# Adder_Subtracter.net
KiCad netlist of a schematic drawn in Altium Designer
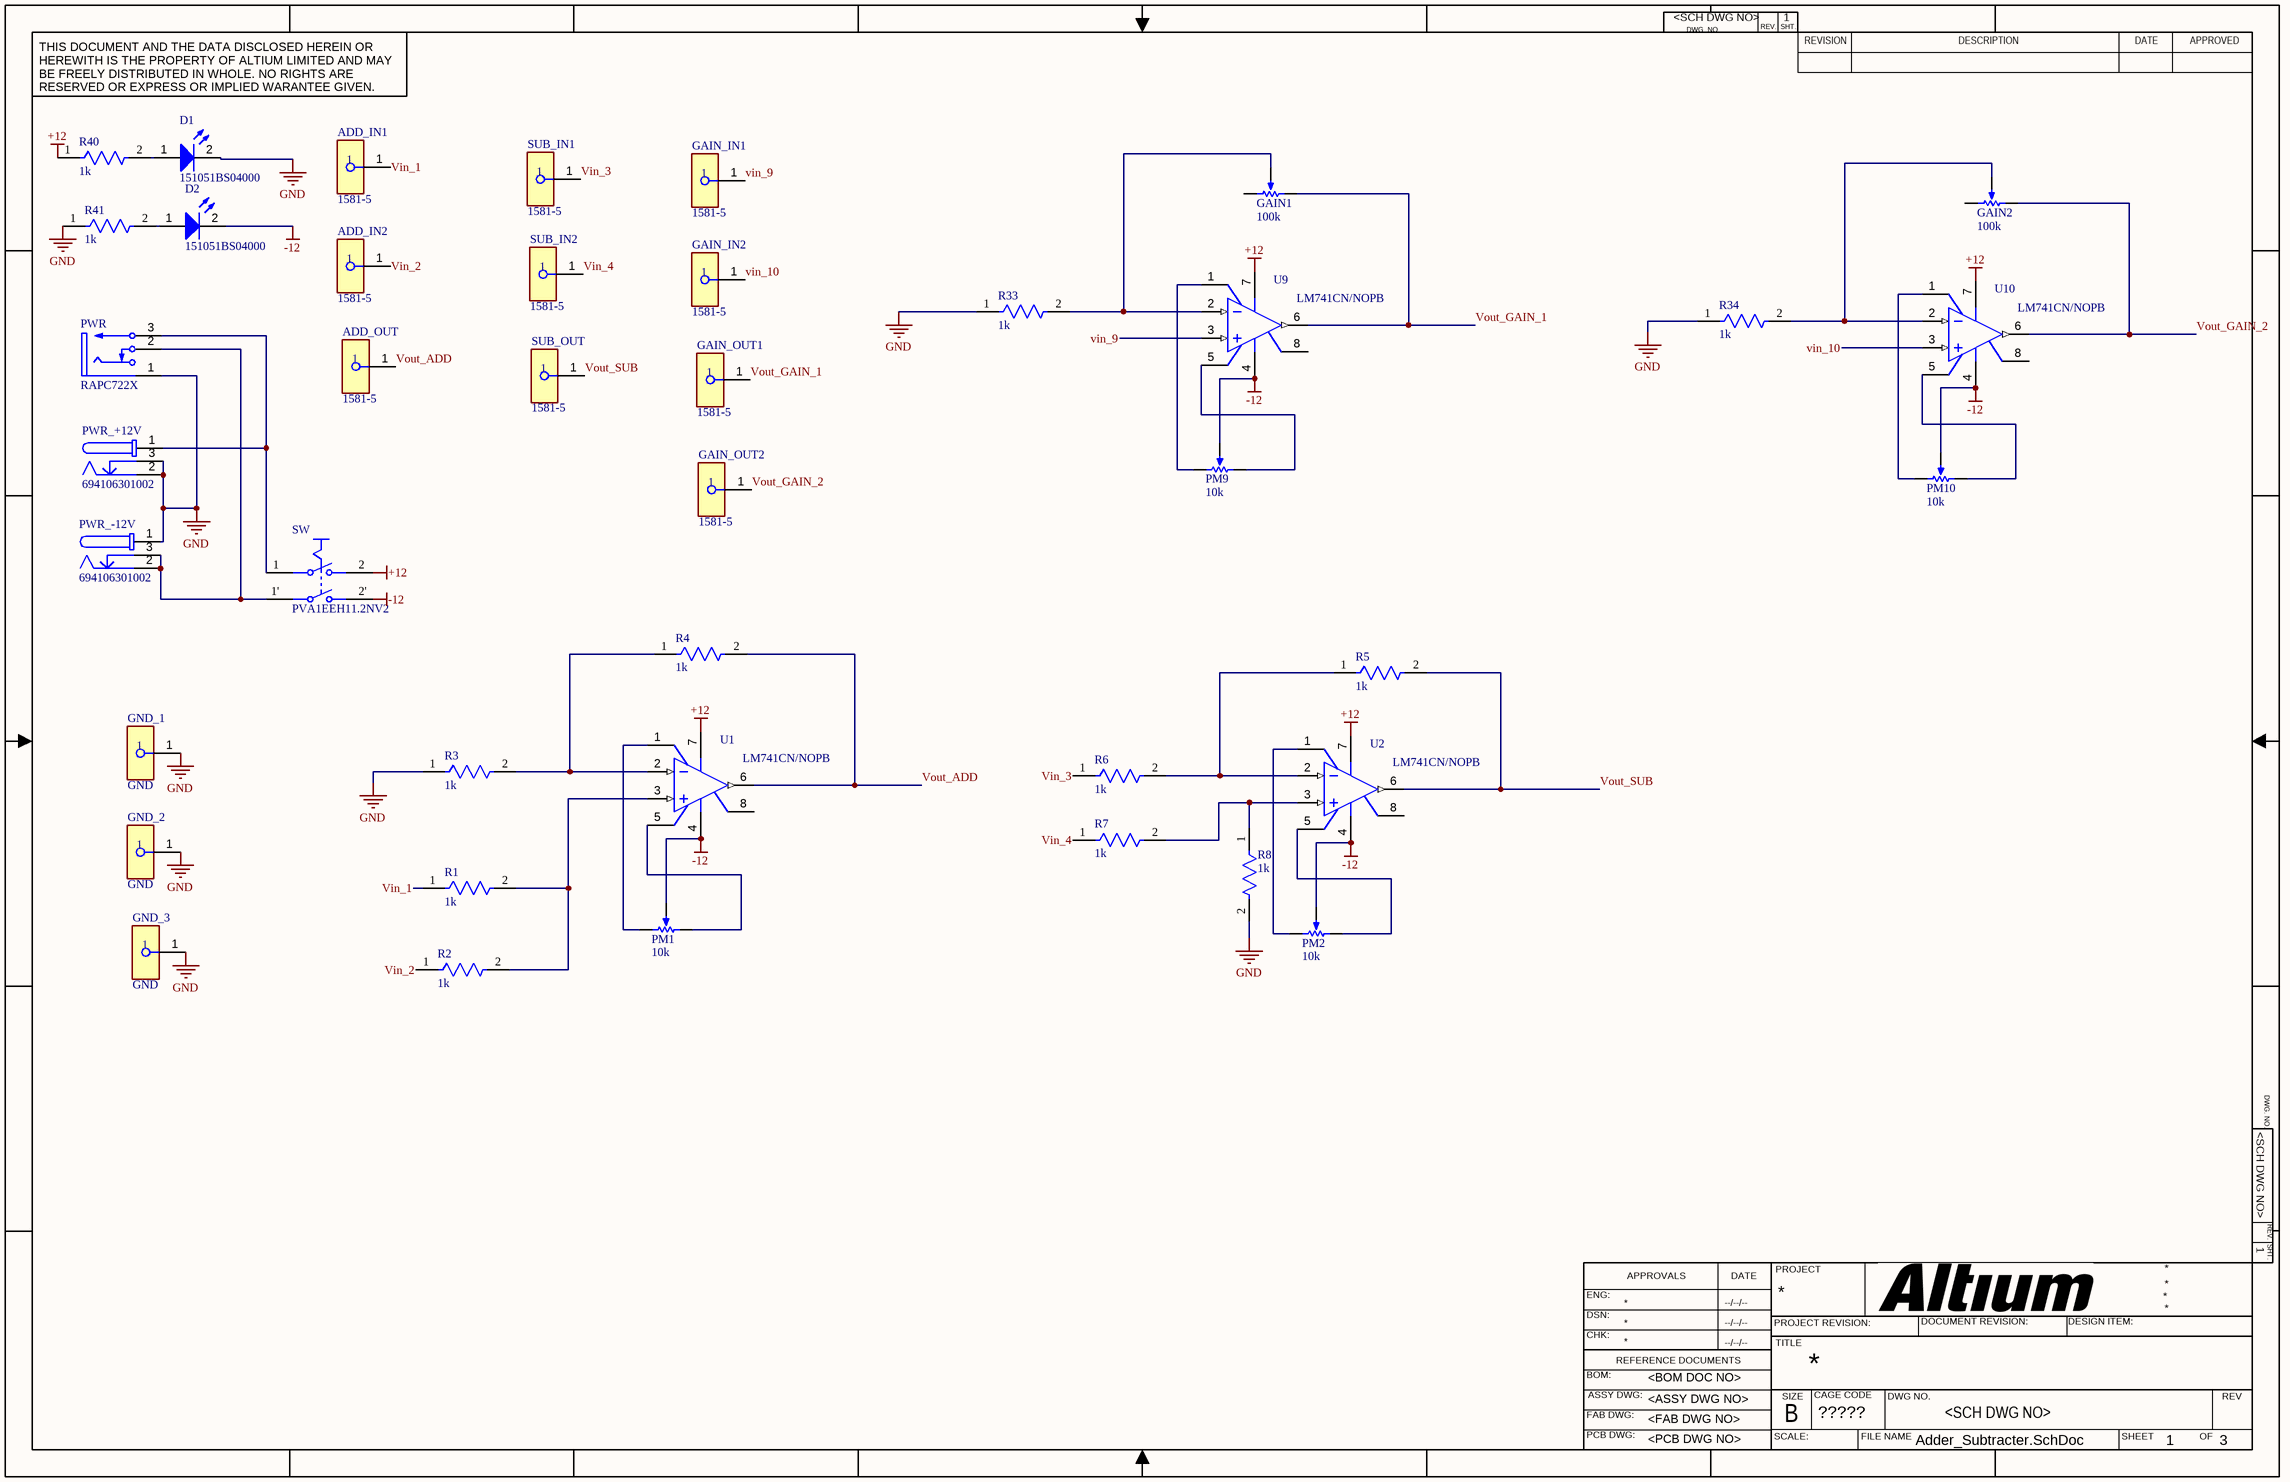
[diagram p0: Adder_Subtracter.SchDoc]

(export (version "E")
  (design (tool "Eeschema 10.0.6"))
  (components
    (comp (ref "ADD_IN1")
      (value "1581-5")
      (footprint "FP-1581-5-MFG")
      (description "CONN BANANA JACK TURRET GREEN")
      (libsource (lib "Altium Content Vault") (part "c5c826e0c4b67fe3b42ef77f2d4decc"))
    )
    (comp (ref "ADD_IN2")
      (value "1581-5")
      (footprint "FP-1581-5-MFG")
      (description "CONN BANANA JACK TURRET GREEN")
      (libsource (lib "Altium Content Vault") (part "c5c826e0c4b67fe3b42ef77f2d4decc"))
    )
    (comp (ref "ADD_OUT")
      (value "1581-5")
      (footprint "FP-1581-5-MFG")
      (description "CONN BANANA JACK TURRET GREEN")
      (libsource (lib "Altium Content Vault") (part "c5c826e0c4b67fe3b42ef77f2d4decc"))
    )
    (comp (ref "D1")
      (value "151051BS04000")
      (footprint "WL-TMRC_D5.9H8.7")
      (libsource (lib "Altium Content Vault") (part "LED_Blue_1A-2K"))
    )
    (comp (ref "D2")
      (value "151051BS04000")
      (footprint "WL-TMRC_D5.9H8.7")
      (libsource (lib "Altium Content Vault") (part "LED_Blue_1A-2K"))
    )
    (comp (ref "GAIN1")
      (value "100k")
      (footprint "BOUR-3852A-282-103AL-3_V")
      (description "Diameter Panel Control, 10 KOhm, +/- 10%, 2 W, -1 to 125 degC, 3-Pin THD, RoHS, Bulk")
      (fields (field (name "TOLERANCE") "±10%") (field (name "MANUFACTURER") "Bourns"))
      (libsource (lib "Altium Content Vault") (part "RES-POT-3"))
    )
    (comp (ref "GAIN2")
      (value "100k")
      (footprint "BOUR-3852A-282-103AL-3_V")
      (description "Diameter Panel Control, 10 KOhm, +/- 10%, 2 W, -1 to 125 degC, 3-Pin THD, RoHS, Bulk")
      (fields (field (name "TOLERANCE") "±10%") (field (name "MANUFACTURER") "Bourns"))
      (libsource (lib "Altium Content Vault") (part "RES-POT-3"))
    )
    (comp (ref "GAIN_IN1")
      (value "1581-5")
      (footprint "FP-1581-5-MFG")
      (description "CONN BANANA JACK TURRET GREEN")
      (libsource (lib "Altium Content Vault") (part "c5c826e0c4b67fe3b42ef77f2d4decc"))
    )
    (comp (ref "GAIN_IN2")
      (value "1581-5")
      (footprint "FP-1581-5-MFG")
      (description "CONN BANANA JACK TURRET GREEN")
      (libsource (lib "Altium Content Vault") (part "c5c826e0c4b67fe3b42ef77f2d4decc"))
    )
    (comp (ref "GAIN_OUT1")
      (value "1581-5")
      (footprint "FP-1581-5-MFG")
      (description "CONN BANANA JACK TURRET GREEN")
      (libsource (lib "Altium Content Vault") (part "c5c826e0c4b67fe3b42ef77f2d4decc"))
    )
    (comp (ref "GAIN_OUT2")
      (value "1581-5")
      (footprint "FP-1581-5-MFG")
      (description "CONN BANANA JACK TURRET GREEN")
      (libsource (lib "Altium Content Vault") (part "c5c826e0c4b67fe3b42ef77f2d4decc"))
    )
    (comp (ref "GND_1")
      (value "GND")
      (footprint "FP-1581-5-MFG")
      (description "CONN BANANA JACK TURRET GREEN")
      (libsource (lib "Altium Content Vault") (part "c5c826e0c4b67fe3b42ef77f2d4decc"))
    )
    (comp (ref "GND_2")
      (value "GND")
      (footprint "FP-1581-5-MFG")
      (description "CONN BANANA JACK TURRET GREEN")
      (libsource (lib "Altium Content Vault") (part "c5c826e0c4b67fe3b42ef77f2d4decc"))
    )
    (comp (ref "GND_3")
      (value "GND")
      (footprint "FP-1581-5-MFG")
      (description "CONN BANANA JACK TURRET GREEN")
      (libsource (lib "Altium Content Vault") (part "c5c826e0c4b67fe3b42ef77f2d4decc"))
    )
    (comp (ref "PM1")
      (value "10k")
      (footprint "BOUR-3362P")
      (description "Square Trimpot(R) Trimming Potentiometer, 10 KOhm, 300 V, -55 to 125 degC, 3-Pin THD, RoHS, Tube")
      (fields (field (name "TOLERANCE") "1%"))
      (libsource (lib "Altium Content Vault") (part "RES-POT-3"))
    )
    (comp (ref "PM2")
      (value "10k")
      (footprint "BOUR-3362P")
      (description "Square Trimpot(R) Trimming Potentiometer, 10 KOhm, 300 V, -55 to 125 degC, 3-Pin THD, RoHS, Tube")
      (fields (field (name "TOLERANCE") "1%"))
      (libsource (lib "Altium Content Vault") (part "RES-POT-3"))
    )
    (comp (ref "PM9")
      (value "10k")
      (footprint "BOUR-3362P")
      (description "Square Trimpot(R) Trimming Potentiometer, 10 KOhm, 300 V, -55 to 125 degC, 3-Pin THD, RoHS, Tube")
      (fields (field (name "TOLERANCE") "1%"))
      (libsource (lib "Altium Content Vault") (part "RES-POT-3"))
    )
    (comp (ref "PM10")
      (value "10k")
      (footprint "BOUR-3362P")
      (description "Square Trimpot(R) Trimming Potentiometer, 10 KOhm, 300 V, -55 to 125 degC, 3-Pin THD, RoHS, Tube")
      (fields (field (name "TOLERANCE") "1%"))
      (libsource (lib "Altium Content Vault") (part "RES-POT-3"))
    )
    (comp (ref "PWR")
      (value "RAPC722X")
      (footprint "SWITCH-RAPC712X-3_V")
      (description "Power Jack, 5 A, 3-Pin THD, RoHS, Bulk")
      (fields (field (name "MANUFACTURER") "Switchcraft"))
      (libsource (lib "Altium Content Vault") (part "SWITCH-RAPC712X-3"))
    )
    (comp (ref "PWR_+12V")
      (value "694106301002")
      (footprint "694106301002")
      (libsource (lib "Altium Content Vault") (part "DC Power Jack"))
    )
    (comp (ref "PWR_-12V")
      (value "694106301002")
      (footprint "694106301002")
      (libsource (lib "Altium Content Vault") (part "DC Power Jack"))
    )
    (comp (ref "R1")
      (value "1k")
      (footprint "FP-RLR07-MFG")
      (fields (field (name "TOLERANCE") "1%"))
      (libsource (lib "Altium Content Vault") (part "1029c3af85768c4190bb7ad29bc67b5"))
    )
    (comp (ref "R2")
      (value "1k")
      (footprint "FP-RLR07-MFG")
      (fields (field (name "TOLERANCE") "1%"))
      (libsource (lib "Altium Content Vault") (part "1029c3af85768c4190bb7ad29bc67b5"))
    )
    (comp (ref "R3")
      (value "1k")
      (footprint "FP-RLR07-MFG")
      (fields (field (name "TOLERANCE") "1%"))
      (libsource (lib "Altium Content Vault") (part "1029c3af85768c4190bb7ad29bc67b5"))
    )
    (comp (ref "R4")
      (value "1k")
      (footprint "FP-RLR07-MFG")
      (fields (field (name "TOLERANCE") "1%"))
      (libsource (lib "Altium Content Vault") (part "1029c3af85768c4190bb7ad29bc67b5"))
    )
    (comp (ref "R5")
      (value "1k")
      (footprint "FP-RLR07-MFG")
      (fields (field (name "TOLERANCE") "1%"))
      (libsource (lib "Altium Content Vault") (part "1029c3af85768c4190bb7ad29bc67b5"))
    )
    (comp (ref "R6")
      (value "1k")
      (footprint "FP-RLR07-MFG")
      (fields (field (name "TOLERANCE") "1%"))
      (libsource (lib "Altium Content Vault") (part "1029c3af85768c4190bb7ad29bc67b5"))
    )
    (comp (ref "R7")
      (value "1k")
      (footprint "FP-RLR07-MFG")
      (fields (field (name "TOLERANCE") "1%"))
      (libsource (lib "Altium Content Vault") (part "1029c3af85768c4190bb7ad29bc67b5"))
    )
    (comp (ref "R8")
      (value "1k")
      (footprint "FP-RLR07-MFG")
      (fields (field (name "TOLERANCE") "1%"))
      (libsource (lib "Altium Content Vault") (part "1029c3af85768c4190bb7ad29bc67b5"))
    )
    (comp (ref "R33")
      (value "1k")
      (footprint "FP-RLR07-MFG")
      (fields (field (name "TOLERANCE") "1%"))
      (libsource (lib "Altium Content Vault") (part "1029c3af85768c4190bb7ad29bc67b5"))
    )
    (comp (ref "R34")
      (value "1k")
      (footprint "FP-RLR07-MFG")
      (fields (field (name "TOLERANCE") "1%"))
      (libsource (lib "Altium Content Vault") (part "1029c3af85768c4190bb7ad29bc67b5"))
    )
    (comp (ref "R40")
      (value "1k")
      (footprint "FP-RLR07-MFG")
      (fields (field (name "TOLERANCE") "1%"))
      (libsource (lib "Altium Content Vault") (part "1029c3af85768c4190bb7ad29bc67b5"))
    )
    (comp (ref "R41")
      (value "1k")
      (footprint "FP-RLR07-MFG")
      (fields (field (name "TOLERANCE") "1%"))
      (libsource (lib "Altium Content Vault") (part "1029c3af85768c4190bb7ad29bc67b5"))
    )
    (comp (ref "SUB_IN1")
      (value "1581-5")
      (footprint "FP-1581-5-MFG")
      (description "CONN BANANA JACK TURRET GREEN")
      (libsource (lib "Altium Content Vault") (part "c5c826e0c4b67fe3b42ef77f2d4decc"))
    )
    (comp (ref "SUB_IN2")
      (value "1581-5")
      (footprint "FP-1581-5-MFG")
      (description "CONN BANANA JACK TURRET GREEN")
      (libsource (lib "Altium Content Vault") (part "c5c826e0c4b67fe3b42ef77f2d4decc"))
    )
    (comp (ref "SUB_OUT")
      (value "1581-5")
      (footprint "FP-1581-5-MFG")
      (description "CONN BANANA JACK TURRET GREEN")
      (libsource (lib "Altium Content Vault") (part "c5c826e0c4b67fe3b42ef77f2d4decc"))
    )
    (comp (ref "SW")
      (value "PVA1EEH11.2NV2")
      (footprint "FP-PVA1EEH11_2NV2-MFG")
      (description "SWITCH PUSH DPST 0.1A 32V")
      (libsource (lib "Altium Content Vault") (part "0a7b0f685d7af6e0316c3509192f32d"))
    )
    (comp (ref "U1")
      (value "LM741CN/NOPB")
      (footprint "P0008A")
      (description "Operational Amplifier, 8-pin MDIP, Pb-Free")
      (fields (field (name "MANUFACTURER") "Texas Instruments"))
      (libsource (lib "Altium Content Vault") (part "AMP-OPA-LM741-8"))
    )
    (comp (ref "U2")
      (value "LM741CN/NOPB")
      (footprint "P0008A")
      (description "Operational Amplifier, 8-pin MDIP, Pb-Free")
      (fields (field (name "MANUFACTURER") "Texas Instruments"))
      (libsource (lib "Altium Content Vault") (part "AMP-OPA-LM741-8"))
    )
    (comp (ref "U9")
      (value "LM741CN/NOPB")
      (footprint "P0008A")
      (description "Operational Amplifier, 8-pin MDIP, Pb-Free")
      (fields (field (name "MANUFACTURER") "Texas Instruments"))
      (libsource (lib "Altium Content Vault") (part "AMP-OPA-LM741-8"))
    )
    (comp (ref "U10")
      (value "LM741CN/NOPB")
      (footprint "P0008A")
      (description "Operational Amplifier, 8-pin MDIP, Pb-Free")
      (fields (field (name "MANUFACTURER") "Texas Instruments"))
      (libsource (lib "Altium Content Vault") (part "AMP-OPA-LM741-8"))
    )
  )
  (nets
    (net (code "1") (name "+12") (class "Default")
      (node (ref "R40") (pin "1") (pinfunction "1_1") (pintype "passive"))
      (node (ref "SW") (pin "2") (pinfunction "2_2") (pintype "passive"))
      (node (ref "U1") (pin "7") (pinfunction "V+_7") (pintype "power_in"))
      (node (ref "U10") (pin "7") (pinfunction "V+_7") (pintype "power_in"))
      (node (ref "U2") (pin "7") (pinfunction "V+_7") (pintype "power_in"))
      (node (ref "U9") (pin "7") (pinfunction "V+_7") (pintype "power_in"))
    )
    (net (code "2") (name "-12") (class "Default")
      (node (ref "D2") (pin "2") (pinfunction "K_2") (pintype "passive"))
      (node (ref "PM1") (pin "2") (pinfunction "S_2") (pintype "passive"))
      (node (ref "PM10") (pin "2") (pinfunction "S_2") (pintype "passive"))
      (node (ref "PM2") (pin "2") (pinfunction "S_2") (pintype "passive"))
      (node (ref "PM9") (pin "2") (pinfunction "S_2") (pintype "passive"))
      (node (ref "SW") (pin "2'") (pinfunction "2'_2'") (pintype "passive"))
      (node (ref "U1") (pin "4") (pinfunction "V-_4") (pintype "power_in"))
      (node (ref "U10") (pin "4") (pinfunction "V-_4") (pintype "power_in"))
      (node (ref "U2") (pin "4") (pinfunction "V-_4") (pintype "power_in"))
      (node (ref "U9") (pin "4") (pinfunction "V-_4") (pintype "power_in"))
    )
    (net (code "3") (name "/Vin_1") (class "Default")
      (node (ref "ADD_IN1") (pin "1") (pinfunction "1_1") (pintype "passive"))
      (node (ref "R1") (pin "1") (pinfunction "1_1") (pintype "passive"))
    )
    (net (code "4") (name "/Vin_2") (class "Default")
      (node (ref "ADD_IN2") (pin "1") (pinfunction "1_1") (pintype "passive"))
      (node (ref "R2") (pin "1") (pinfunction "1_1") (pintype "passive"))
    )
    (net (code "5") (name "/Vin_3") (class "Default")
      (node (ref "R6") (pin "1") (pinfunction "1_1") (pintype "passive"))
      (node (ref "SUB_IN1") (pin "1") (pinfunction "1_1") (pintype "passive"))
    )
    (net (code "6") (name "/Vin_4") (class "Default")
      (node (ref "R7") (pin "1") (pinfunction "1_1") (pintype "passive"))
      (node (ref "SUB_IN2") (pin "1") (pinfunction "1_1") (pintype "passive"))
    )
    (net (code "7") (name "/Vout_ADD") (class "Default")
      (node (ref "ADD_OUT") (pin "1") (pinfunction "1_1") (pintype "passive"))
      (node (ref "R4") (pin "2") (pinfunction "2_2") (pintype "passive"))
      (node (ref "U1") (pin "6") (pinfunction "OUT_6") (pintype "output"))
    )
    (net (code "8") (name "/Vout_GAIN_1") (class "Default")
      (node (ref "GAIN1") (pin "1") (pinfunction "CCW_1") (pintype "passive"))
      (node (ref "GAIN_OUT1") (pin "1") (pinfunction "1_1") (pintype "passive"))
      (node (ref "U9") (pin "6") (pinfunction "OUT_6") (pintype "output"))
    )
    (net (code "9") (name "/Vout_GAIN_2") (class "Default")
      (node (ref "GAIN2") (pin "1") (pinfunction "CCW_1") (pintype "passive"))
      (node (ref "GAIN_OUT2") (pin "1") (pinfunction "1_1") (pintype "passive"))
      (node (ref "U10") (pin "6") (pinfunction "OUT_6") (pintype "output"))
    )
    (net (code "10") (name "/Vout_SUB") (class "Default")
      (node (ref "R5") (pin "2") (pinfunction "2_2") (pintype "passive"))
      (node (ref "SUB_OUT") (pin "1") (pinfunction "1_1") (pintype "passive"))
      (node (ref "U2") (pin "6") (pinfunction "OUT_6") (pintype "output"))
    )
    (net (code "11") (name "/vin_9") (class "Default")
      (node (ref "GAIN_IN1") (pin "1") (pinfunction "1_1") (pintype "passive"))
      (node (ref "U9") (pin "3") (pinfunction "IN+_3") (pintype "input"))
    )
    (net (code "12") (name "/vin_10") (class "Default")
      (node (ref "GAIN_IN2") (pin "1") (pinfunction "1_1") (pintype "passive"))
      (node (ref "U10") (pin "3") (pinfunction "IN+_3") (pintype "input"))
    )
    (net (code "13") (name "GND") (class "Default")
      (node (ref "D1") (pin "2") (pinfunction "K_2") (pintype "passive"))
      (node (ref "GND_1") (pin "1") (pinfunction "1_1") (pintype "passive"))
      (node (ref "GND_2") (pin "1") (pinfunction "1_1") (pintype "passive"))
      (node (ref "GND_3") (pin "1") (pinfunction "1_1") (pintype "passive"))
      (node (ref "PWR") (pin "1") (pinfunction "1_1") (pintype "passive"))
      (node (ref "PWR_+12V") (pin "2") (pinfunction "2_2") (pintype "passive"))
      (node (ref "PWR_+12V") (pin "3") (pinfunction "3_3") (pintype "passive"))
      (node (ref "PWR_-12V") (pin "1") (pinfunction "1_1") (pintype "passive"))
      (node (ref "R3") (pin "1") (pinfunction "1_1") (pintype "passive"))
      (node (ref "R33") (pin "1") (pinfunction "1_1") (pintype "passive"))
      (node (ref "R34") (pin "1") (pinfunction "1_1") (pintype "passive"))
      (node (ref "R41") (pin "1") (pinfunction "1_1") (pintype "passive"))
      (node (ref "R8") (pin "2") (pinfunction "2_2") (pintype "passive"))
    )
    (net (code "14") (name "Net-(D1-A)") (class "Default")
      (node (ref "D1") (pin "1") (pinfunction "A_1") (pintype "passive"))
      (node (ref "R40") (pin "2") (pinfunction "2_2") (pintype "passive"))
    )
    (net (code "15") (name "Net-(D2-A)") (class "Default")
      (node (ref "D2") (pin "1") (pinfunction "A_1") (pintype "passive"))
      (node (ref "R41") (pin "2") (pinfunction "2_2") (pintype "passive"))
    )
    (net (code "16") (name "Net-(GAIN1-S)") (class "Default")
      (node (ref "GAIN1") (pin "2") (pinfunction "S_2") (pintype "passive"))
      (node (ref "R33") (pin "2") (pinfunction "2_2") (pintype "passive"))
      (node (ref "U9") (pin "2") (pinfunction "IN-_2") (pintype "input"))
    )
    (net (code "17") (name "Net-(GAIN2-S)") (class "Default")
      (node (ref "GAIN2") (pin "2") (pinfunction "S_2") (pintype "passive"))
      (node (ref "R34") (pin "2") (pinfunction "2_2") (pintype "passive"))
      (node (ref "U10") (pin "2") (pinfunction "IN-_2") (pintype "input"))
    )
    (net (code "18") (name "Net-(PM1-CCW)") (class "Default")
      (node (ref "PM1") (pin "1") (pinfunction "CCW_1") (pintype "passive"))
      (node (ref "U1") (pin "5") (pinfunction "OFS_NULL_5") (pintype "passive"))
    )
    (net (code "19") (name "Net-(PM1-CW)") (class "Default")
      (node (ref "PM1") (pin "3") (pinfunction "CW_3") (pintype "passive"))
      (node (ref "U1") (pin "1") (pinfunction "OFS_NULL_1") (pintype "passive"))
    )
    (net (code "20") (name "Net-(PM2-CCW)") (class "Default")
      (node (ref "PM2") (pin "1") (pinfunction "CCW_1") (pintype "passive"))
      (node (ref "U2") (pin "5") (pinfunction "OFS_NULL_5") (pintype "passive"))
    )
    (net (code "21") (name "Net-(PM2-CW)") (class "Default")
      (node (ref "PM2") (pin "3") (pinfunction "CW_3") (pintype "passive"))
      (node (ref "U2") (pin "1") (pinfunction "OFS_NULL_1") (pintype "passive"))
    )
    (net (code "22") (name "Net-(PM9-CCW)") (class "Default")
      (node (ref "PM9") (pin "1") (pinfunction "CCW_1") (pintype "passive"))
      (node (ref "U9") (pin "5") (pinfunction "OFS_NULL_5") (pintype "passive"))
    )
    (net (code "23") (name "Net-(PM9-CW)") (class "Default")
      (node (ref "PM9") (pin "3") (pinfunction "CW_3") (pintype "passive"))
      (node (ref "U9") (pin "1") (pinfunction "OFS_NULL_1") (pintype "passive"))
    )
    (net (code "24") (name "Net-(PM10-CCW)") (class "Default")
      (node (ref "PM10") (pin "1") (pinfunction "CCW_1") (pintype "passive"))
      (node (ref "U10") (pin "5") (pinfunction "OFS_NULL_5") (pintype "passive"))
    )
    (net (code "25") (name "Net-(PM10-CW)") (class "Default")
      (node (ref "PM10") (pin "3") (pinfunction "CW_3") (pintype "passive"))
      (node (ref "U10") (pin "1") (pinfunction "OFS_NULL_1") (pintype "passive"))
    )
    (net (code "26") (name "Net-(PWR-Pad2)") (class "Default")
      (node (ref "PWR") (pin "2") (pinfunction "2_2") (pintype "passive"))
      (node (ref "PWR_-12V") (pin "2") (pinfunction "2_2") (pintype "passive"))
      (node (ref "PWR_-12V") (pin "3") (pinfunction "3_3") (pintype "passive"))
      (node (ref "SW") (pin "1'") (pinfunction "1'_1'") (pintype "passive"))
    )
    (net (code "27") (name "Net-(PWR-Pad3)") (class "Default")
      (node (ref "PWR") (pin "3") (pinfunction "3_3") (pintype "passive"))
      (node (ref "PWR_+12V") (pin "1") (pinfunction "1_1") (pintype "passive"))
      (node (ref "SW") (pin "1") (pinfunction "1_1") (pintype "passive"))
    )
    (net (code "28") (name "Net-(U1-IN+)") (class "Default")
      (node (ref "R1") (pin "2") (pinfunction "2_2") (pintype "passive"))
      (node (ref "R2") (pin "2") (pinfunction "2_2") (pintype "passive"))
      (node (ref "U1") (pin "3") (pinfunction "IN+_3") (pintype "input"))
    )
    (net (code "29") (name "Net-(U1-IN-)") (class "Default")
      (node (ref "R3") (pin "2") (pinfunction "2_2") (pintype "passive"))
      (node (ref "R4") (pin "1") (pinfunction "1_1") (pintype "passive"))
      (node (ref "U1") (pin "2") (pinfunction "IN-_2") (pintype "input"))
    )
    (net (code "30") (name "Net-(U2-IN+)") (class "Default")
      (node (ref "R7") (pin "2") (pinfunction "2_2") (pintype "passive"))
      (node (ref "R8") (pin "1") (pinfunction "1_1") (pintype "passive"))
      (node (ref "U2") (pin "3") (pinfunction "IN+_3") (pintype "input"))
    )
    (net (code "31") (name "Net-(U2-IN-)") (class "Default")
      (node (ref "R5") (pin "1") (pinfunction "1_1") (pintype "passive"))
      (node (ref "R6") (pin "2") (pinfunction "2_2") (pintype "passive"))
      (node (ref "U2") (pin "2") (pinfunction "IN-_2") (pintype "input"))
    )
    (net (code "32") (name "unconnected-(GAIN1-CW-Pad3)") (class "Default")
      (node (ref "GAIN1") (pin "3") (pinfunction "CW_3") (pintype "passive"))
    )
    (net (code "33") (name "unconnected-(GAIN2-CW-Pad3)") (class "Default")
      (node (ref "GAIN2") (pin "3") (pinfunction "CW_3") (pintype "passive"))
    )
    (net (code "34") (name "unconnected-(U1-NC-Pad8)") (class "Default")
      (node (ref "U1") (pin "8") (pinfunction "NC_8") (pintype "passive"))
    )
    (net (code "35") (name "unconnected-(U2-NC-Pad8)") (class "Default")
      (node (ref "U2") (pin "8") (pinfunction "NC_8") (pintype "passive"))
    )
    (net (code "36") (name "unconnected-(U9-NC-Pad8)") (class "Default")
      (node (ref "U9") (pin "8") (pinfunction "NC_8") (pintype "passive"))
    )
    (net (code "37") (name "unconnected-(U10-NC-Pad8)") (class "Default")
      (node (ref "U10") (pin "8") (pinfunction "NC_8") (pintype "passive"))
    )
  )
)
